# PCB_Telemetria_2020.net
KiCad netlist of a schematic drawn in EAGLE
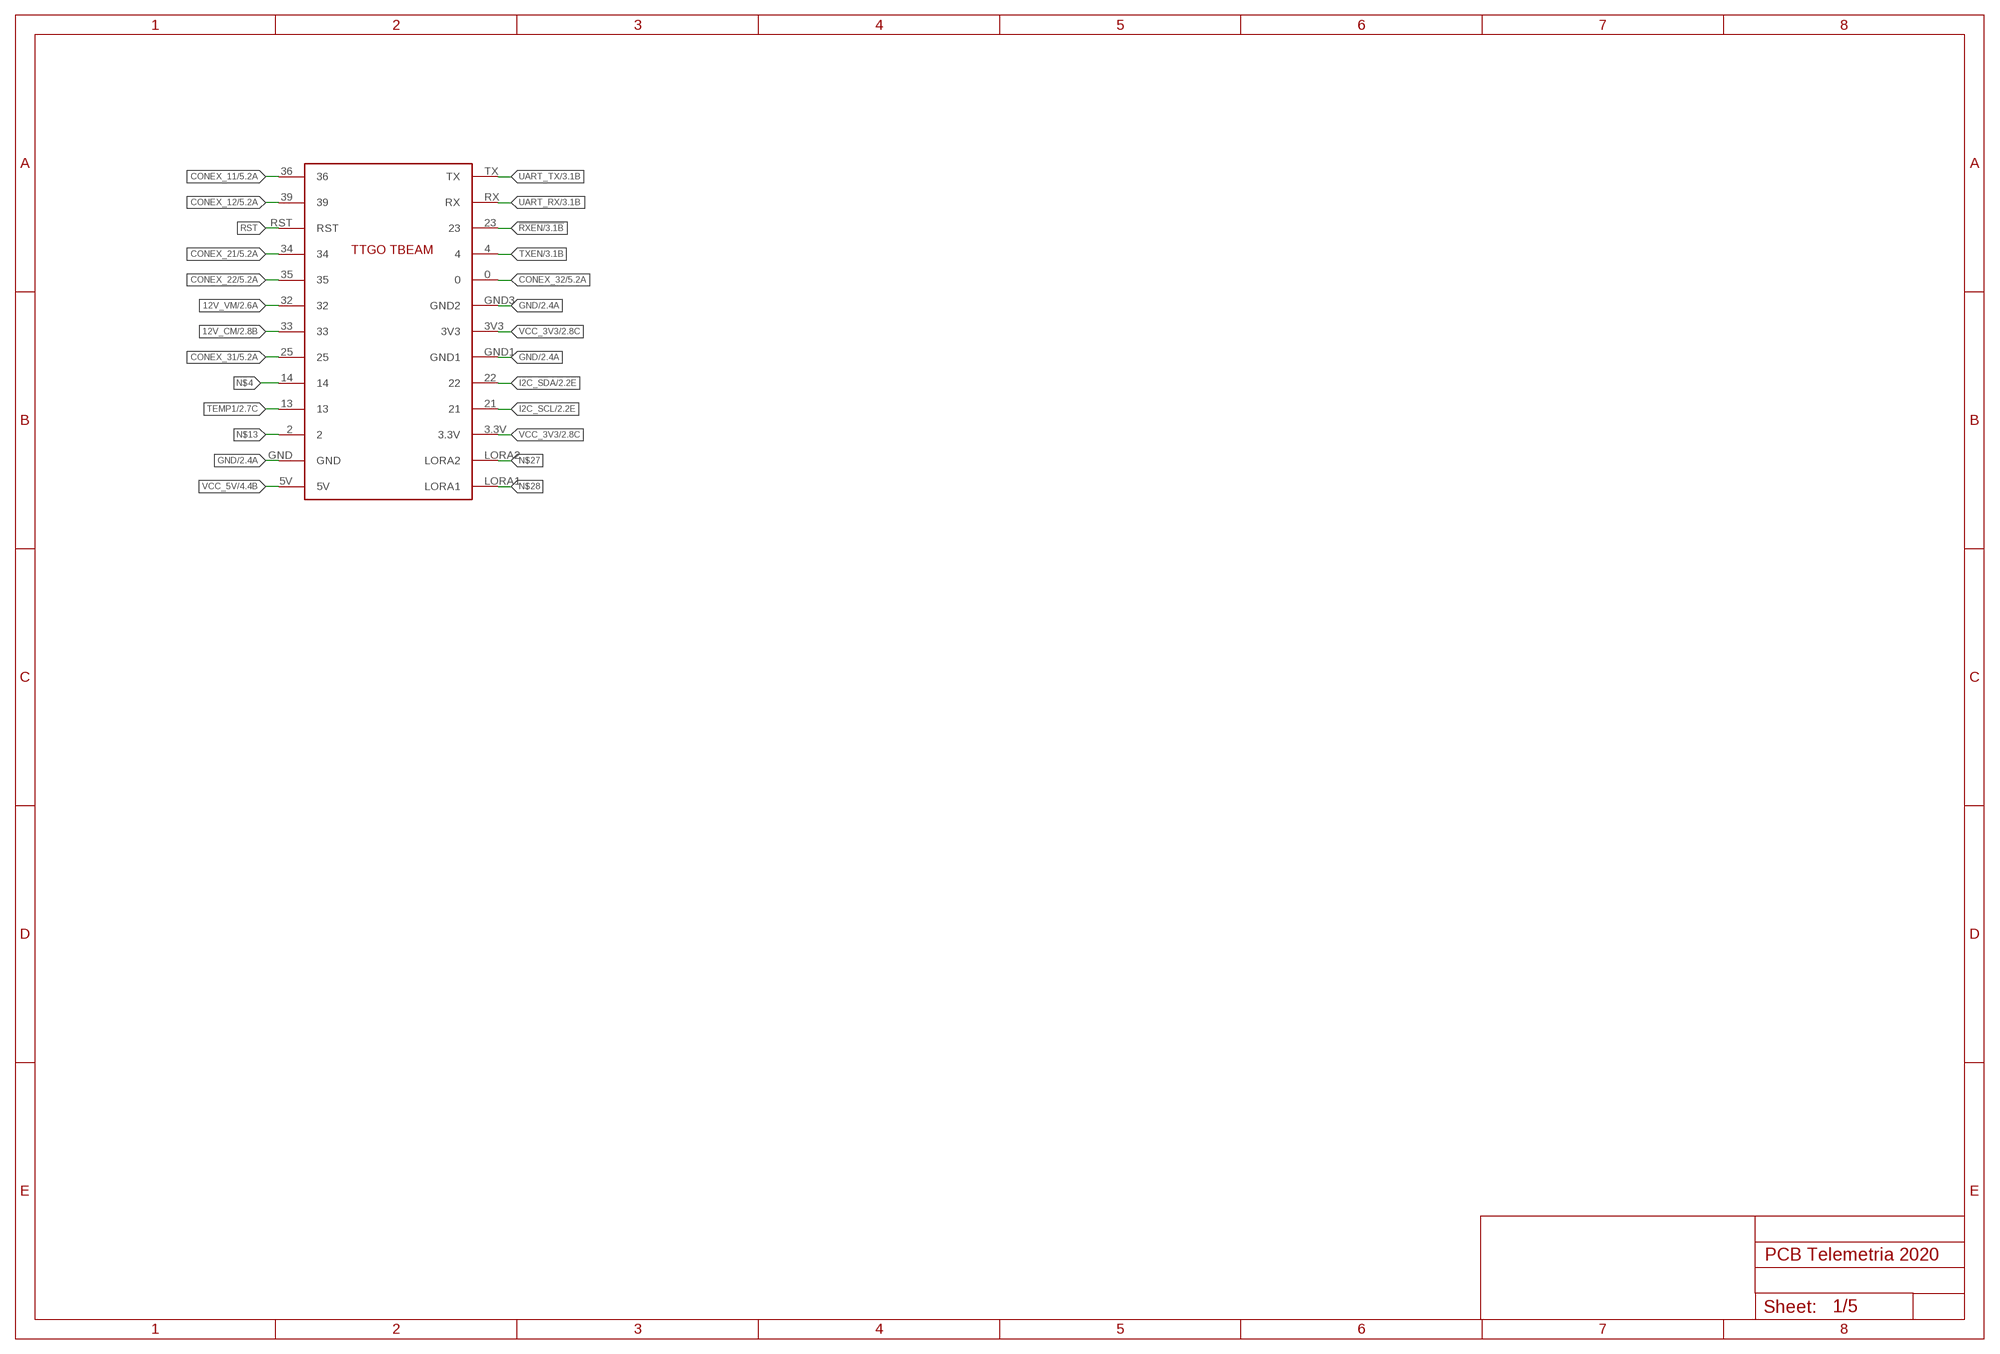
[diagram p0: schematic, sheet 1]
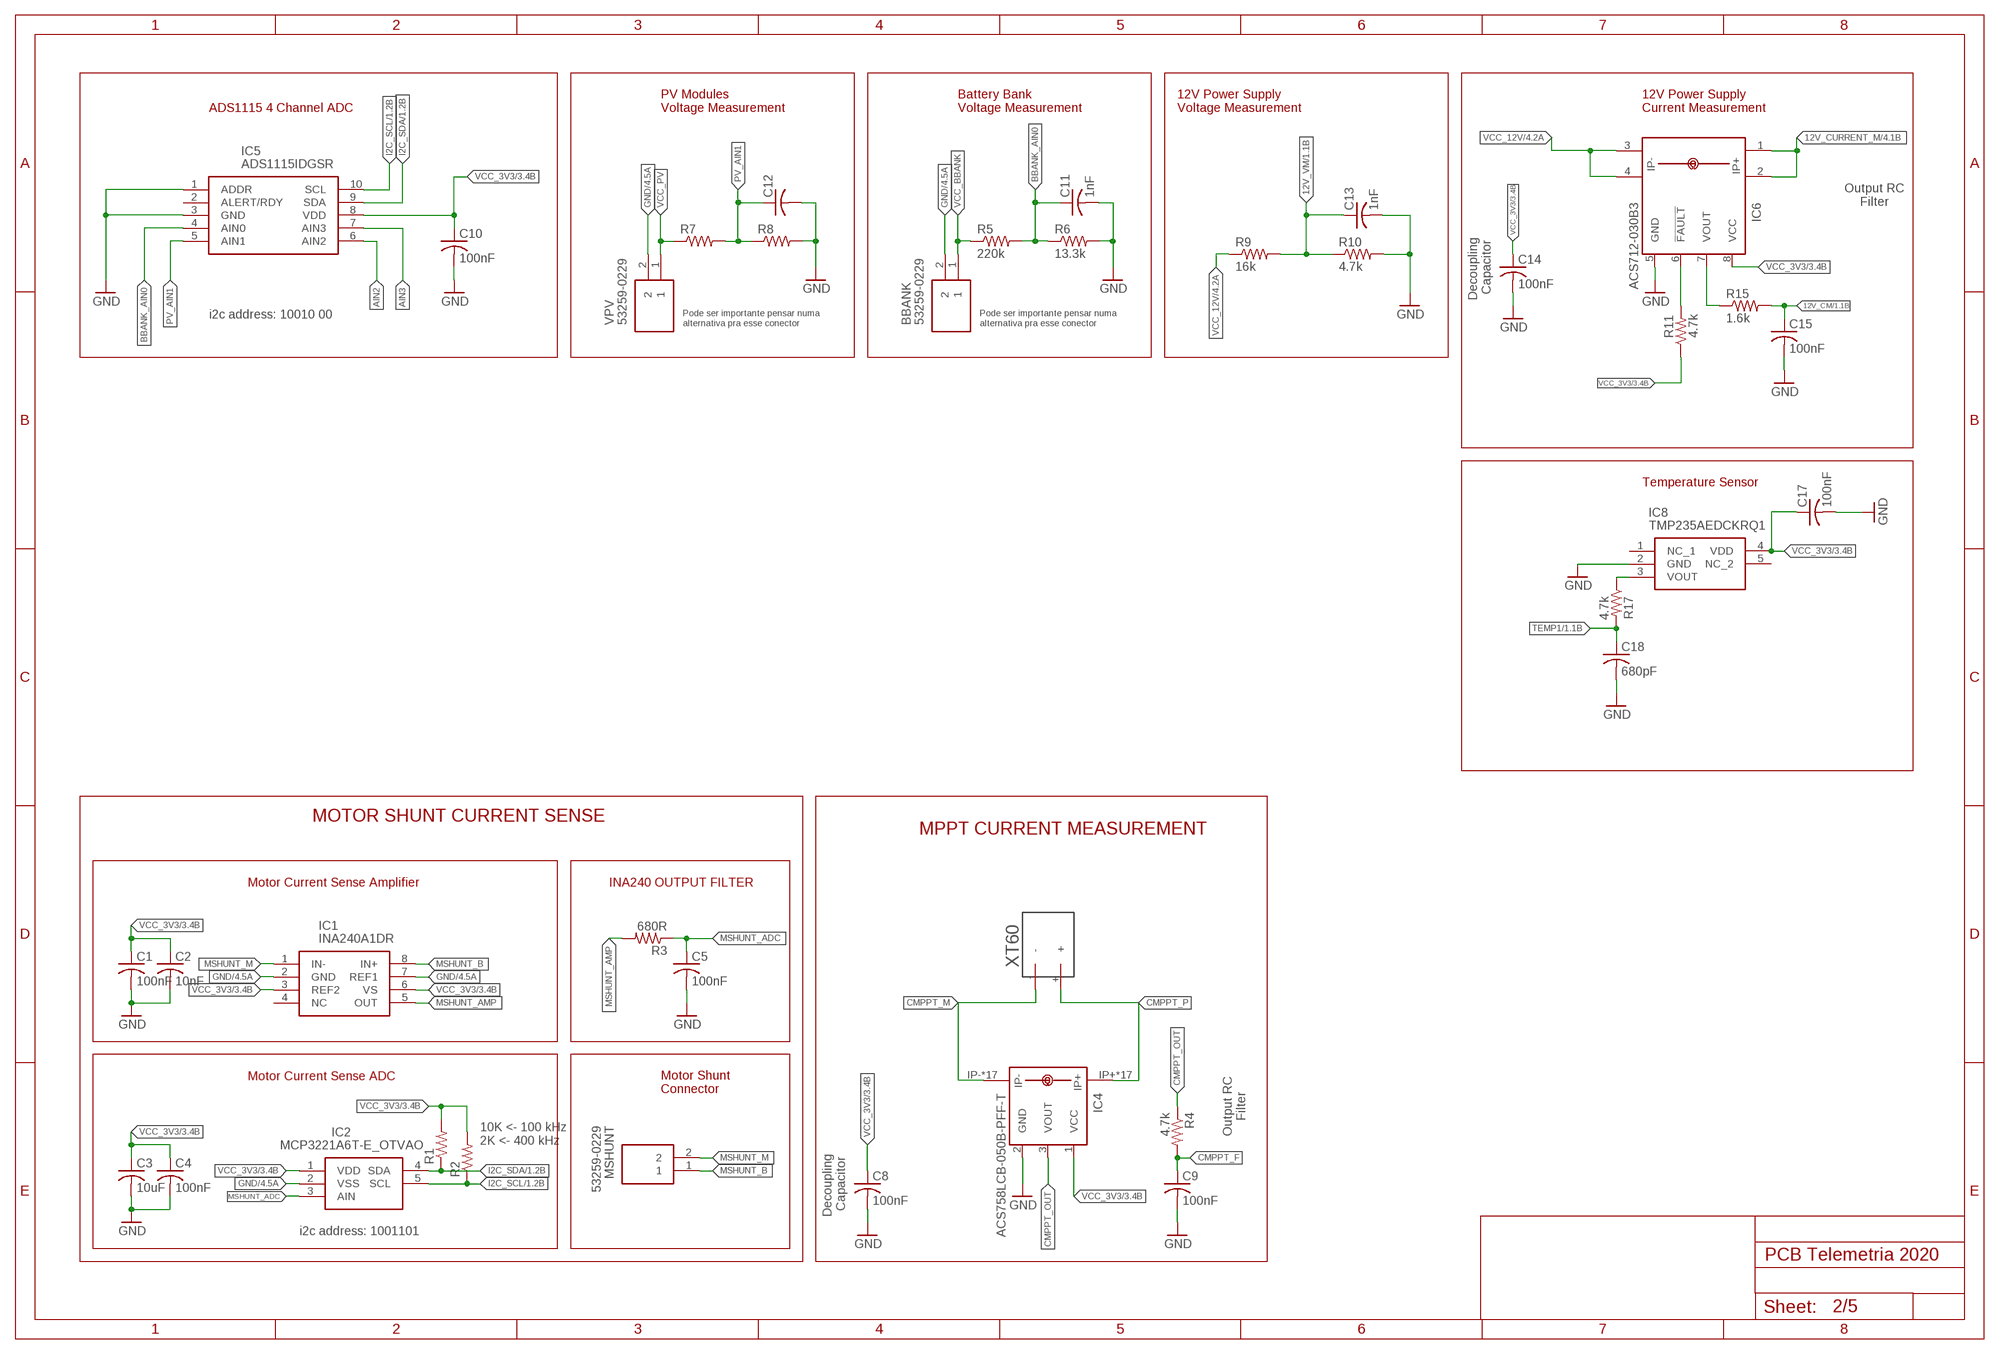
[diagram p1: schematic, sheet 2]
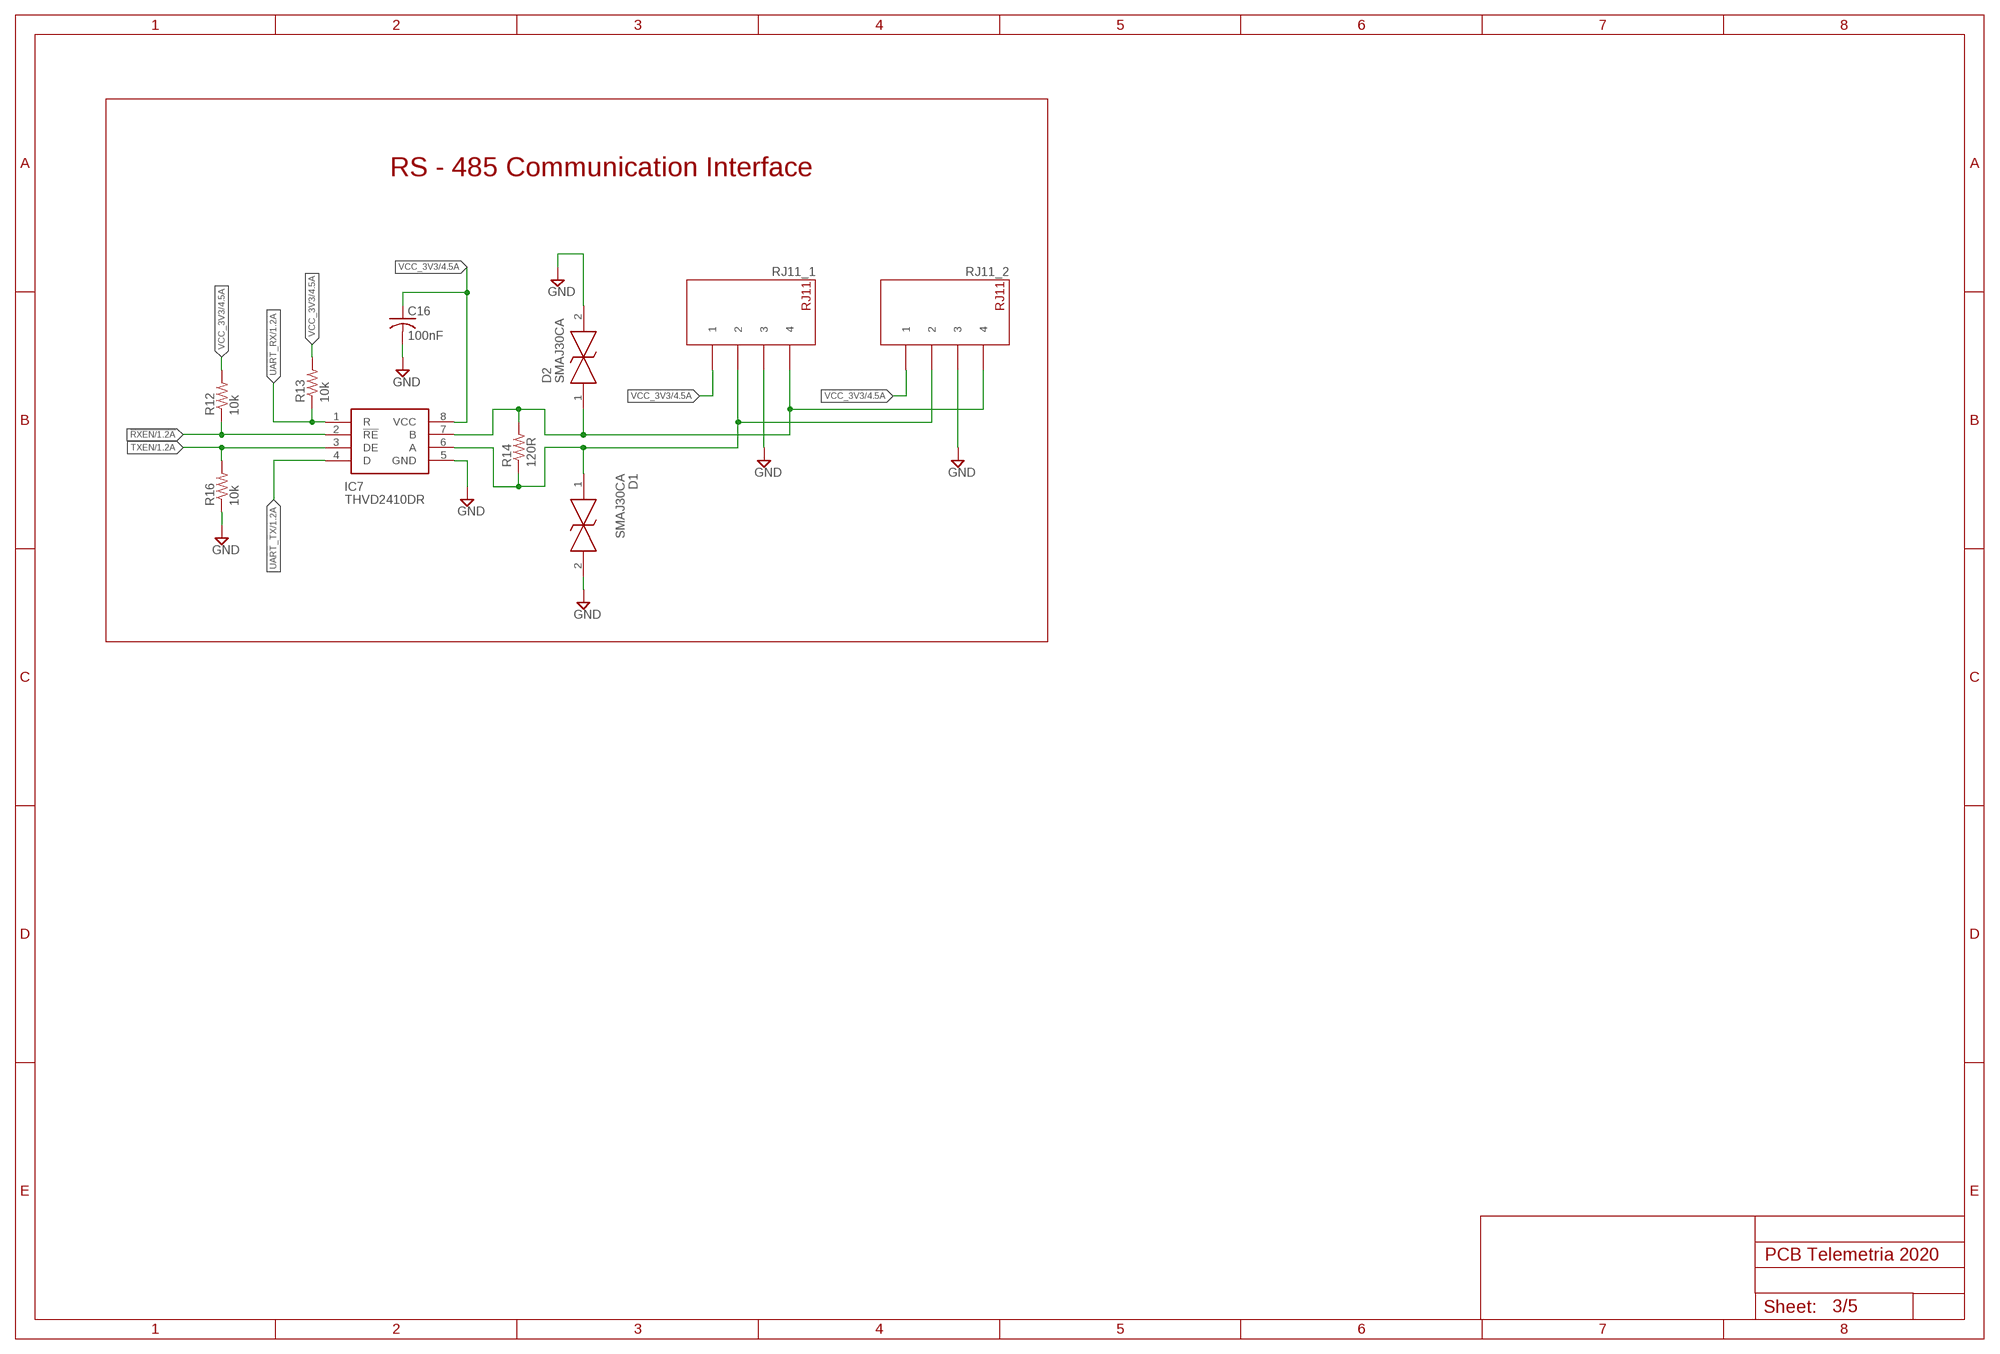
[diagram p2: schematic, sheet 3]
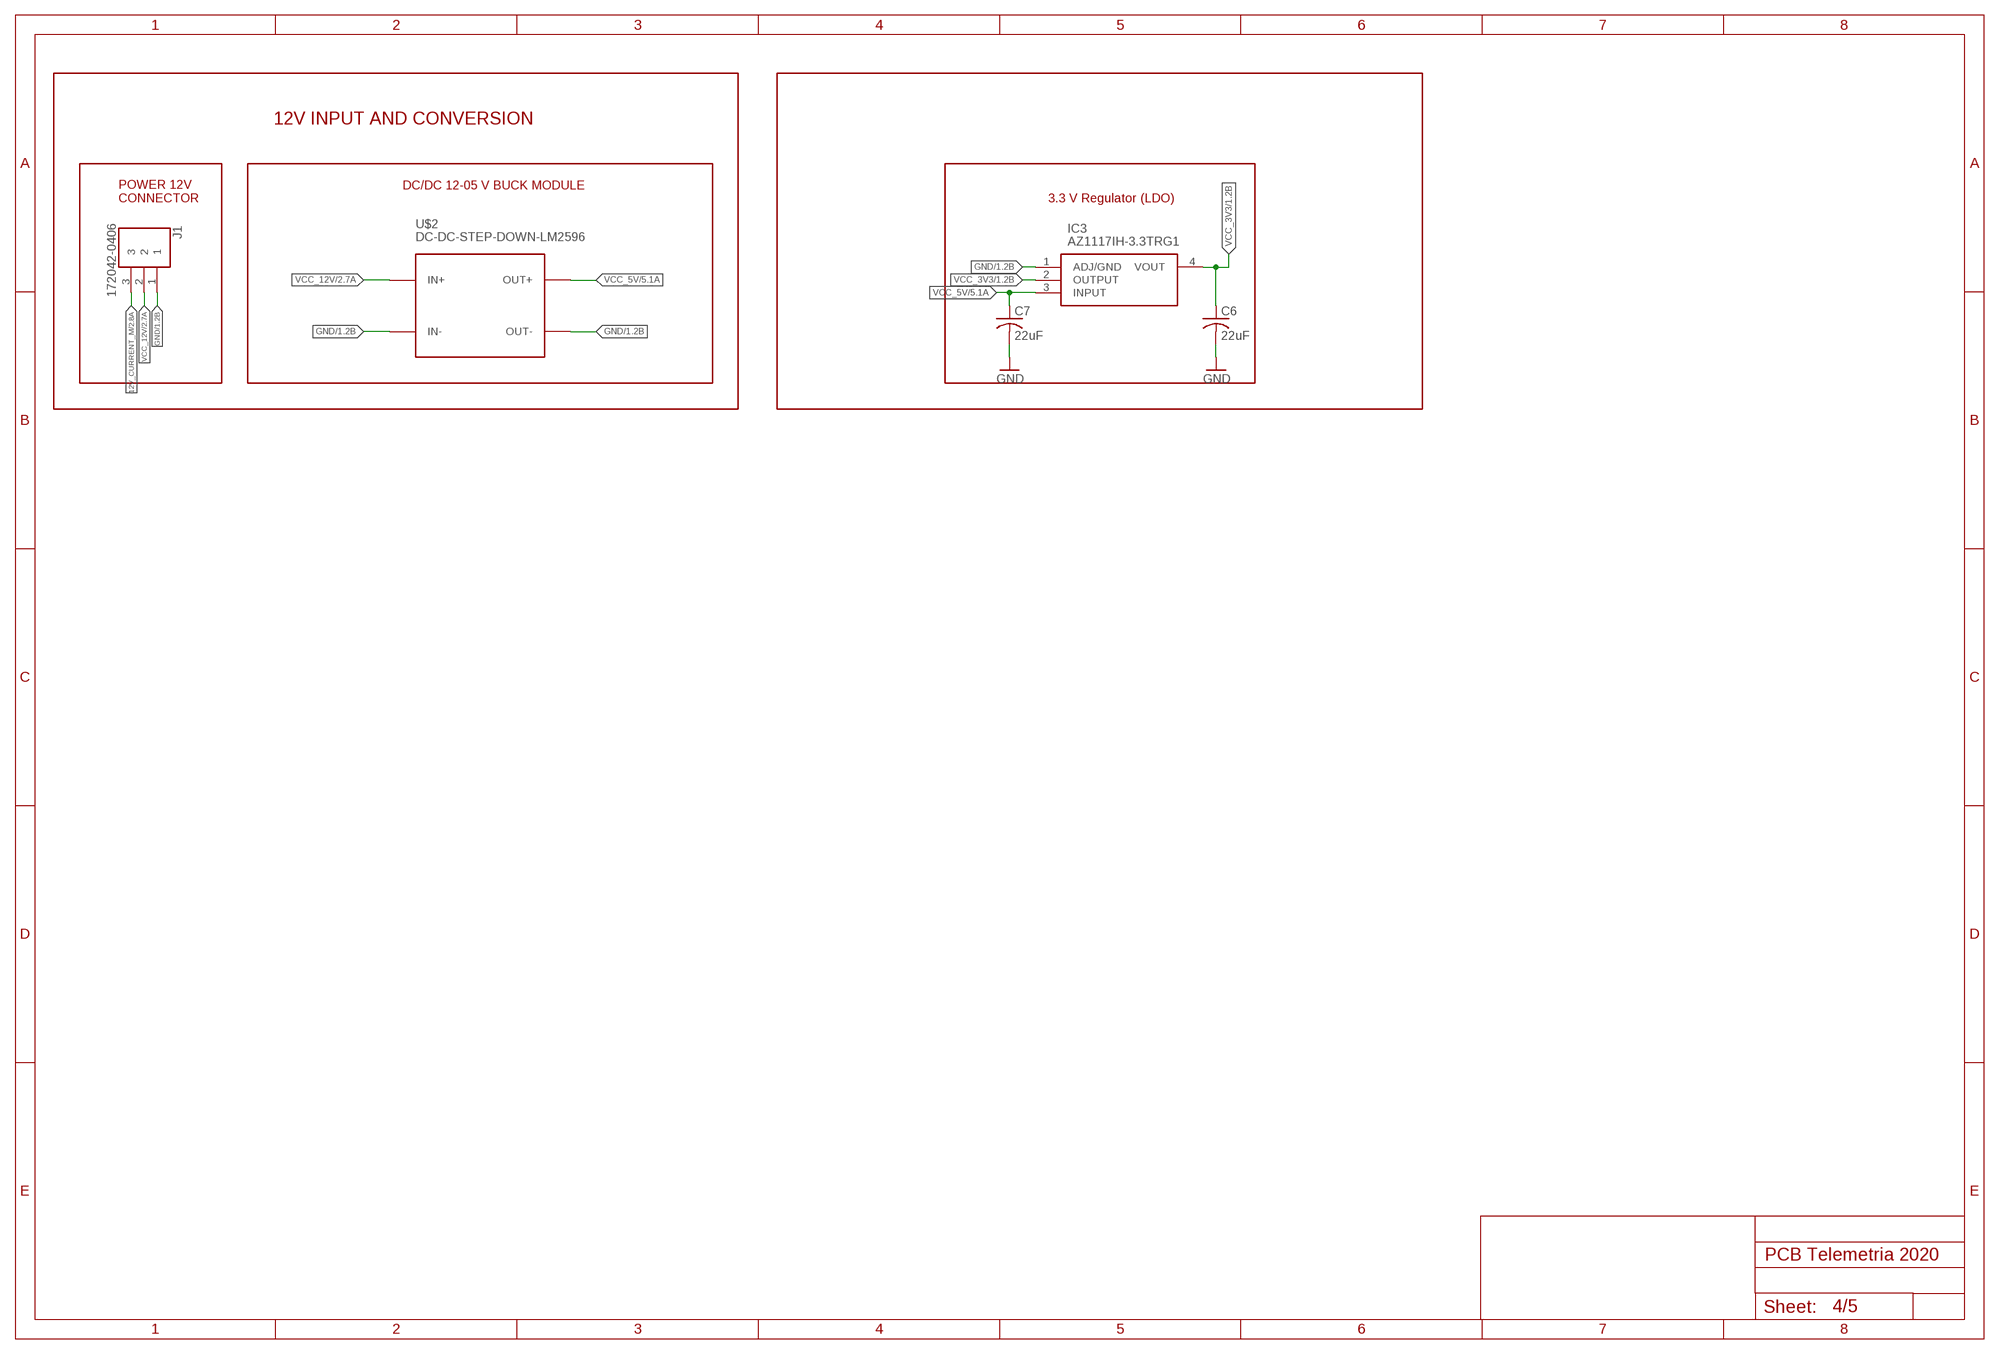
[diagram p3: schematic, sheet 4]
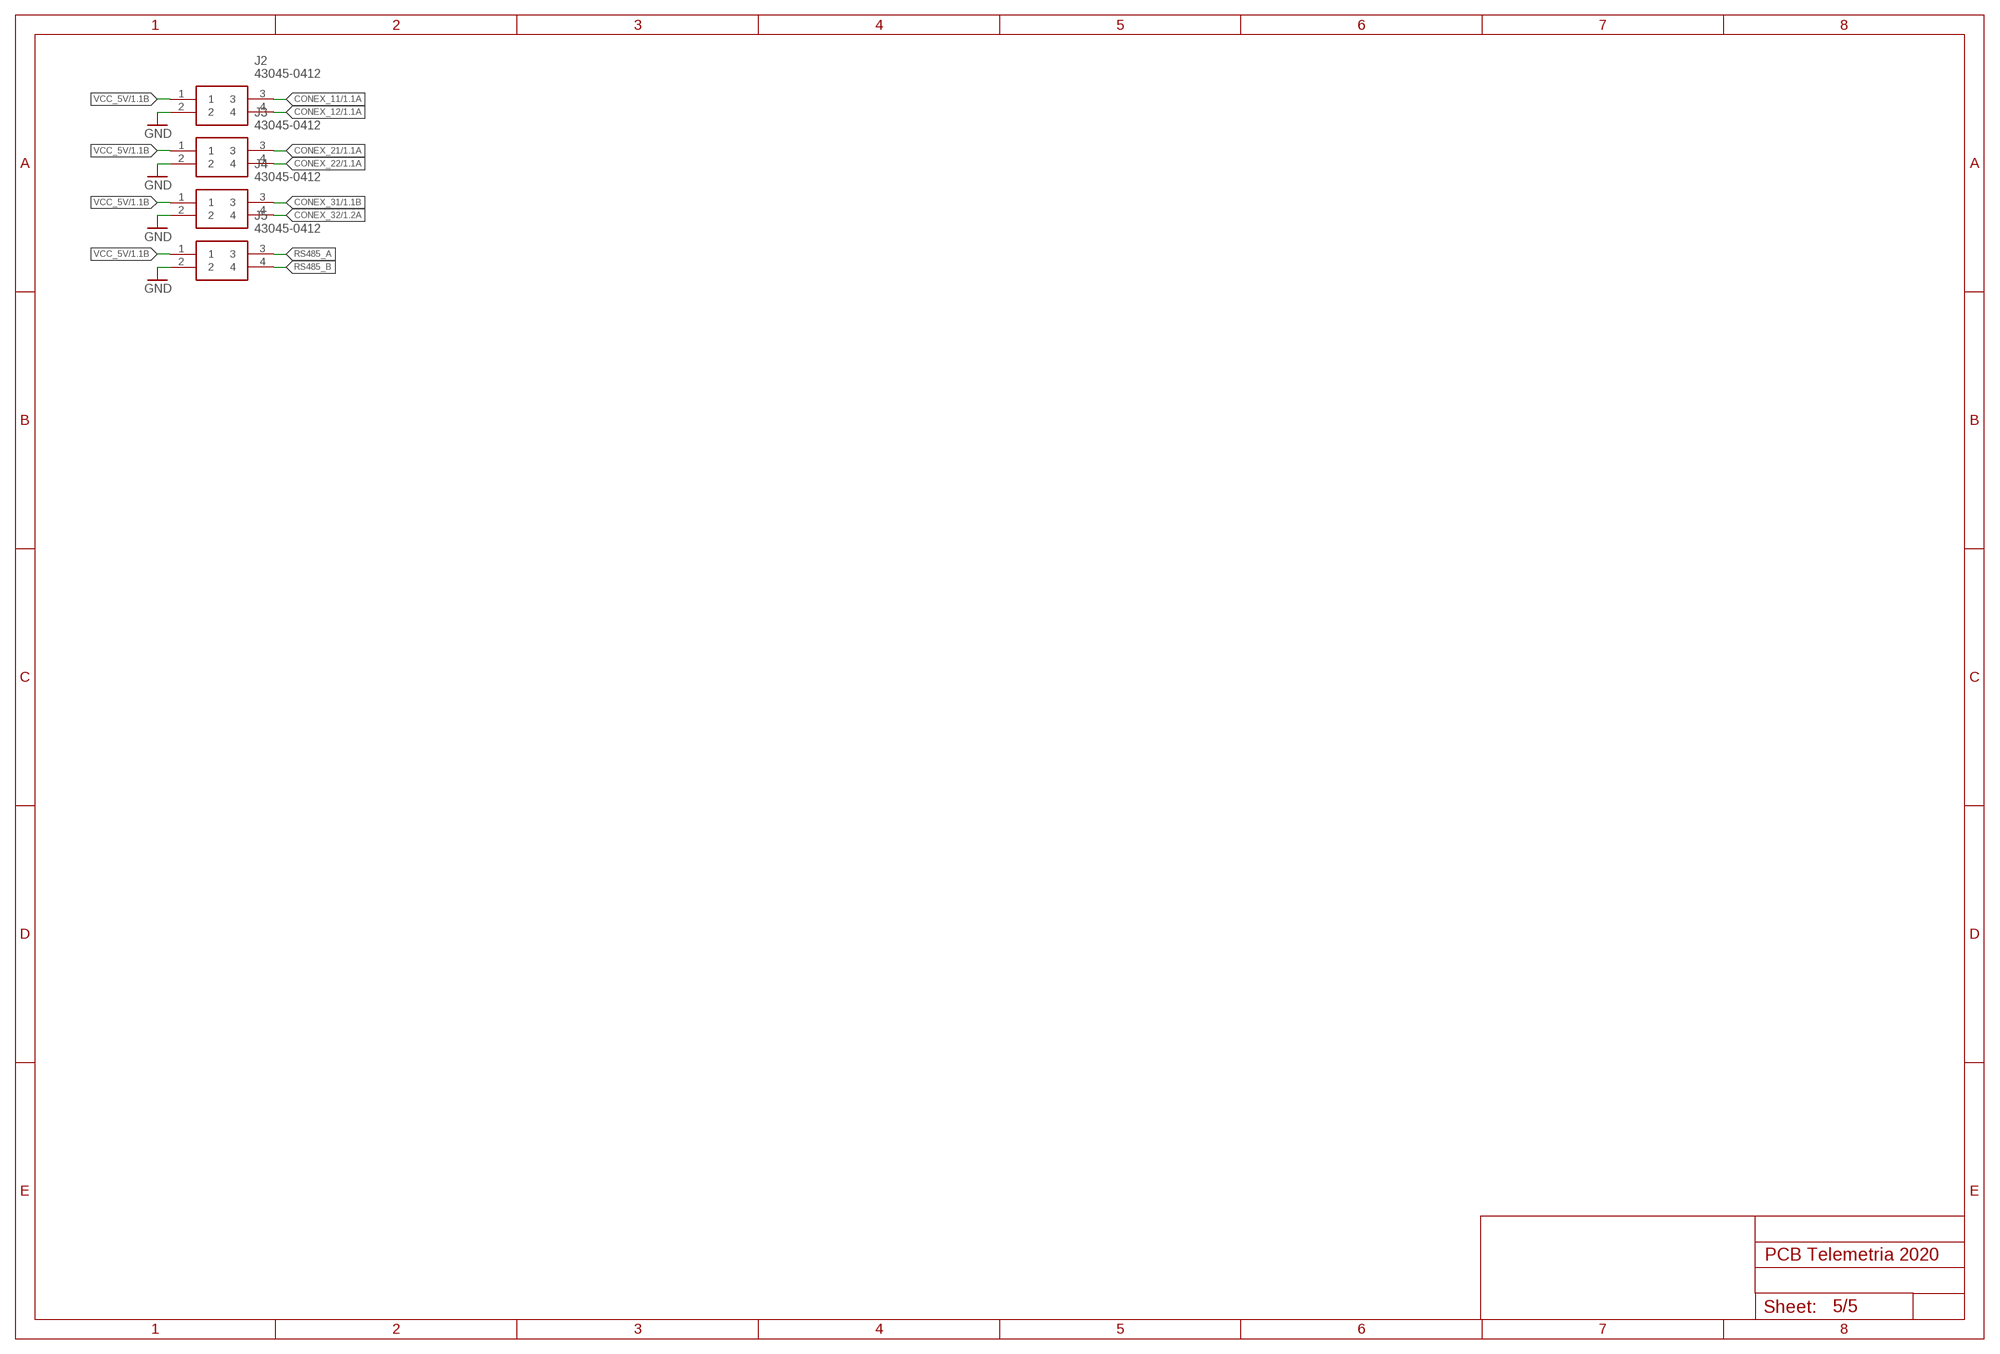
[diagram p4: schematic, sheet 5]

(export (version "E")
  (design (tool "Eeschema 10.0.6"))
  (components
    (comp (ref "U$1")
      (value "TTGOBEAM")
      (footprint "eagle-import:TTGOBEAM")
      (libsource (lib "eagle-import") (part "TTGOBEAM"))
    )
    (comp (ref "J2")
      (value "43045-0412")
      (footprint "eagle-import:43045-0412")
      (fields (field (name "MOUSER_PART_NUMBER") "538-43045-0412"))
      (libsource (lib "eagle-import") (part "43045-0412"))
    )
    (comp (ref "J3")
      (value "43045-0412")
      (footprint "eagle-import:43045-0412")
      (fields (field (name "MOUSER_PART_NUMBER") "538-43045-0412"))
      (libsource (lib "eagle-import") (part "43045-0412"))
    )
    (comp (ref "J4")
      (value "43045-0412")
      (footprint "eagle-import:43045-0412")
      (fields (field (name "MOUSER_PART_NUMBER") "538-43045-0412"))
      (libsource (lib "eagle-import") (part "43045-0412"))
    )
    (comp (ref "J5")
      (value "43045-0412")
      (footprint "eagle-import:43045-0412")
      (fields (field (name "MOUSER_PART_NUMBER") "538-43045-0412"))
      (libsource (lib "eagle-import") (part "43045-0412"))
    )
    (comp (ref "BBANK")
      (value "53259-0229")
      (footprint "eagle-import:0532590229")
      (fields (field (name "MOUSER_PART_NUMBER") "538-53259-0229"))
      (libsource (lib "eagle-import") (part "53259-0229"))
    )
    (comp (ref "C1")
      (value "100nF")
      (footprint "eagle-import:C0805")
      (libsource (lib "eagle-import") (part "C-USC0805"))
    )
    (comp (ref "C2")
      (value "10nF")
      (footprint "eagle-import:C0805")
      (libsource (lib "eagle-import") (part "C-USC0805"))
    )
    (comp (ref "C3")
      (value "10uF")
      (footprint "eagle-import:C0805")
      (libsource (lib "eagle-import") (part "C-USC0805"))
    )
    (comp (ref "C4")
      (value "100nF")
      (footprint "eagle-import:C0805")
      (libsource (lib "eagle-import") (part "C-USC0805"))
    )
    (comp (ref "C5")
      (value "100nF")
      (footprint "eagle-import:C0805")
      (libsource (lib "eagle-import") (part "C-USC0805"))
    )
    (comp (ref "C8")
      (value "100nF")
      (footprint "eagle-import:C0805")
      (libsource (lib "eagle-import") (part "C-USC0805"))
    )
    (comp (ref "C9")
      (value "100nF")
      (footprint "eagle-import:C0805")
      (libsource (lib "eagle-import") (part "C-USC0805"))
    )
    (comp (ref "C10")
      (value "100nF")
      (footprint "eagle-import:C0805")
      (libsource (lib "eagle-import") (part "C-USC0805"))
    )
    (comp (ref "C11")
      (value "1nF")
      (footprint "eagle-import:C0805")
      (libsource (lib "eagle-import") (part "C-USC0805"))
    )
    (comp (ref "C12")
      (value "C-USC0805")
      (footprint "eagle-import:C0805")
      (libsource (lib "eagle-import") (part "C-USC0805"))
    )
    (comp (ref "C13")
      (value "1nF")
      (footprint "eagle-import:C0805")
      (libsource (lib "eagle-import") (part "C-USC0805"))
    )
    (comp (ref "C14")
      (value "100nF")
      (footprint "eagle-import:C0805")
      (libsource (lib "eagle-import") (part "C-USC0805"))
    )
    (comp (ref "C15")
      (value "100nF")
      (footprint "eagle-import:C0805")
      (libsource (lib "eagle-import") (part "C-USC0805"))
    )
    (comp (ref "C17")
      (value "100nF")
      (footprint "eagle-import:C0805")
      (libsource (lib "eagle-import") (part "C-USC0805"))
    )
    (comp (ref "C18")
      (value "680pF")
      (footprint "eagle-import:C0805")
      (libsource (lib "eagle-import") (part "C-USC0805"))
    )
    (comp (ref "IC1")
      (value "INA240A1DR")
      (footprint "eagle-import:SOIC127P600X175-8N")
      (fields (field (name "MOUSER_PART_NUMBER") "595-INA240A1DR"))
      (libsource (lib "eagle-import") (part "INA240A1DR"))
    )
    (comp (ref "IC2")
      (value "MCP3221A6T-E_OTVAO")
      (footprint "eagle-import:SOT95P280X145-5N")
      (fields
        (field (name "MANUFACTURER_PART_NUMBER") "MCP3221A6T-E/OTVAO")
        (field (name "MOUSER_PART_NUMBER") "579-MCP3221A6TEOTVAO")
      )
      (libsource (lib "eagle-import") (part "MCP3221A6T-E_OTVAO"))
    )
    (comp (ref "IC4")
      (value "ACS758LCB-050B-PFF-T")
      (footprint "eagle-import:CB-PFF")
      (libsource (lib "eagle-import") (part "ACS758LCB-050B-PFF-T"))
    )
    (comp (ref "IC5")
      (value "ADS1115IDGSR")
      (footprint "eagle-import:SOP50P490X110-10N")
      (fields (field (name "MOUSER_PART_NUMBER") "595-ADS1115IDGSR"))
      (libsource (lib "eagle-import") (part "ADS1115IDGSR"))
    )
    (comp (ref "IC6")
      (value "ACS712-030B3")
      (footprint "eagle-import:SOIC8")
      (libsource (lib "eagle-import") (part "ACS712-LC"))
    )
    (comp (ref "IC8")
      (value "TMP235AEDCKRQ1")
      (footprint "eagle-import:SOT65P210X110-5N")
      (fields (field (name "MOUSER_PART_NUMBER") "595-TMP235AEDCKRQ1"))
      (libsource (lib "eagle-import") (part "TMP235AEDCKRQ1"))
    )
    (comp (ref "MSHUNT")
      (value "53259-0229")
      (footprint "eagle-import:0532590229")
      (fields (field (name "MOUSER_PART_NUMBER") "538-53259-0229"))
      (libsource (lib "eagle-import") (part "53259-0229"))
    )
    (comp (ref "R1")
      (value "R-US_R0805")
      (footprint "eagle-import:R0805")
      (libsource (lib "eagle-import") (part "R-US_R0805"))
    )
    (comp (ref "R2")
      (value "R-US_R0805")
      (footprint "eagle-import:R0805")
      (libsource (lib "eagle-import") (part "R-US_R0805"))
    )
    (comp (ref "R3")
      (value "680R")
      (footprint "eagle-import:R0805")
      (libsource (lib "eagle-import") (part "R-US_R0805"))
    )
    (comp (ref "R4")
      (value "4.7k")
      (footprint "eagle-import:R0805")
      (libsource (lib "eagle-import") (part "R-US_R0805"))
    )
    (comp (ref "R5")
      (value "220k")
      (footprint "eagle-import:R0805")
      (libsource (lib "eagle-import") (part "R-US_R0805"))
    )
    (comp (ref "R6")
      (value "13.3k")
      (footprint "eagle-import:R0805")
      (libsource (lib "eagle-import") (part "R-US_R0805"))
    )
    (comp (ref "R7")
      (value "R-US_R0805")
      (footprint "eagle-import:R0805")
      (libsource (lib "eagle-import") (part "R-US_R0805"))
    )
    (comp (ref "R8")
      (value "R-US_R0805")
      (footprint "eagle-import:R0805")
      (libsource (lib "eagle-import") (part "R-US_R0805"))
    )
    (comp (ref "R9")
      (value "16k")
      (footprint "eagle-import:R0805")
      (libsource (lib "eagle-import") (part "R-US_R0805"))
    )
    (comp (ref "R10")
      (value "4.7k")
      (footprint "eagle-import:R0805")
      (libsource (lib "eagle-import") (part "R-US_R0805"))
    )
    (comp (ref "R11")
      (value "4.7k")
      (footprint "eagle-import:R0805")
      (libsource (lib "eagle-import") (part "R-US_R0805"))
    )
    (comp (ref "R15")
      (value "1.6k")
      (footprint "eagle-import:R0805")
      (libsource (lib "eagle-import") (part "R-US_R0805"))
    )
    (comp (ref "R17")
      (value "4.7k")
      (footprint "eagle-import:R0805")
      (libsource (lib "eagle-import") (part "R-US_R0805"))
    )
    (comp (ref "U$3")
      (value "XT60")
      (footprint "eagle-import:XT60")
      (libsource (lib "eagle-import") (part "XT60"))
    )
    (comp (ref "VPV")
      (value "53259-0229")
      (footprint "eagle-import:0532590229")
      (fields (field (name "MOUSER_PART_NUMBER") "538-53259-0229"))
      (libsource (lib "eagle-import") (part "53259-0229"))
    )
    (comp (ref "C6")
      (value "22uF")
      (footprint "eagle-import:C0805")
      (libsource (lib "eagle-import") (part "C-USC0805"))
    )
    (comp (ref "C7")
      (value "22uF")
      (footprint "eagle-import:C0805")
      (libsource (lib "eagle-import") (part "C-USC0805"))
    )
    (comp (ref "IC3")
      (value "AZ1117IH-3.3TRG1")
      (footprint "eagle-import:SOT230P700X170-4N")
      (fields (field (name "MOUSER_PART_NUMBER") "621-AZ1117IH-3.3TRG1"))
      (libsource (lib "eagle-import") (part "AZ1117IH-3.3TRG1"))
    )
    (comp (ref "J1")
      (value "172042-0406")
      (footprint "eagle-import:MOLEX_172042-0406")
      (fields (field (name "MF") "Molex") (field (name "MP") "172042-0302"))
      (libsource (lib "eagle-import") (part "172042-0406"))
    )
    (comp (ref "U$2")
      (value "DC-DC-STEP-DOWN-LM2596")
      (footprint "eagle-import:DC-DC-STEP-DOWN-LM2596")
      (libsource (lib "eagle-import") (part "DC-DC-STEP-DOWN-LM2596"))
    )
    (comp (ref "C16")
      (value "100nF")
      (footprint "eagle-import:C0805")
      (libsource (lib "eagle-import") (part "C-USC0805"))
    )
    (comp (ref "D1")
      (value "SMAJ30CA")
      (footprint "eagle-import:DIONM5026X229N")
      (fields (field (name "MOUSER_PART_NUMBER") "576-SMAJ30CA"))
      (libsource (lib "eagle-import") (part "SMAJ30CA"))
    )
    (comp (ref "D2")
      (value "SMAJ30CA")
      (footprint "eagle-import:DIONM5026X229N")
      (fields (field (name "MOUSER_PART_NUMBER") "576-SMAJ30CA"))
      (libsource (lib "eagle-import") (part "SMAJ30CA"))
    )
    (comp (ref "IC7")
      (value "THVD2410DR")
      (footprint "eagle-import:SOIC127P600X175-8N")
      (fields (field (name "MOUSER_PART_NUMBER") "595-THVD2410DR"))
      (libsource (lib "eagle-import") (part "THVD2410DR"))
    )
    (comp (ref "R12")
      (value "10k")
      (footprint "eagle-import:M0805")
      (libsource (lib "eagle-import") (part "R-US_M0805"))
    )
    (comp (ref "R13")
      (value "10k")
      (footprint "eagle-import:M0805")
      (libsource (lib "eagle-import") (part "R-US_M0805"))
    )
    (comp (ref "R14")
      (value "120R")
      (footprint "eagle-import:M0805")
      (libsource (lib "eagle-import") (part "R-US_M0805"))
    )
    (comp (ref "R16")
      (value "10k")
      (footprint "eagle-import:M0805")
      (libsource (lib "eagle-import") (part "R-US_M0805"))
    )
    (comp (ref "RJ11_1")
      (value "TFC44")
      (footprint "eagle-import:TFC44")
      (libsource (lib "eagle-import") (part "TFC44"))
    )
    (comp (ref "RJ11_2")
      (value "TFC44")
      (footprint "eagle-import:TFC44")
      (libsource (lib "eagle-import") (part "TFC44"))
    )
  )
  (nets
    (net (code "1") (name "12V_CM") (class "Default")
      (node (ref "C15") (pin "1") (pinfunction "1_1") (pintype "passive"))
      (node (ref "R15") (pin "2") (pinfunction "2_2") (pintype "passive"))
      (node (ref "U$1") (pin "33") (pinfunction "33_33") (pintype "bidirectional"))
    )
    (net (code "2") (name "12V_CURRENT_M") (class "Default")
      (node (ref "IC6") (pin "1") (pinfunction "IP+_1") (pintype "passive"))
      (node (ref "IC6") (pin "2") (pinfunction "IP+1_2") (pintype "passive"))
      (node (ref "J1") (pin "3") (pinfunction "3_3") (pintype "passive"))
    )
    (net (code "3") (name "12V_VM") (class "Default")
      (node (ref "C13") (pin "1") (pinfunction "1_1") (pintype "passive"))
      (node (ref "R10") (pin "1") (pinfunction "1_1") (pintype "passive"))
      (node (ref "R9") (pin "2") (pinfunction "2_2") (pintype "passive"))
      (node (ref "U$1") (pin "32") (pinfunction "32_32") (pintype "bidirectional"))
    )
    (net (code "4") (name "AIN2") (class "Default")
      (node (ref "IC5") (pin "6") (pinfunction "AIN2_6") (pintype "bidirectional"))
    )
    (net (code "5") (name "AIN3") (class "Default")
      (node (ref "IC5") (pin "7") (pinfunction "AIN3_7") (pintype "bidirectional"))
    )
    (net (code "6") (name "BBANK_AIN0") (class "Default")
      (node (ref "C11") (pin "1") (pinfunction "1_1") (pintype "passive"))
      (node (ref "IC5") (pin "4") (pinfunction "AIN0_4") (pintype "bidirectional"))
      (node (ref "R5") (pin "2") (pinfunction "2_2") (pintype "passive"))
      (node (ref "R6") (pin "1") (pinfunction "1_1") (pintype "passive"))
    )
    (net (code "7") (name "CMPPT_F") (class "Default")
      (node (ref "C9") (pin "1") (pinfunction "1_1") (pintype "passive"))
      (node (ref "R4") (pin "2") (pinfunction "2_2") (pintype "passive"))
    )
    (net (code "8") (name "CMPPT_M") (class "Default")
      (node (ref "IC4") (pin "IP-") (pinfunction "IP-_IP-") (pintype "passive"))
      (node (ref "IC4") (pin "IP-@10") (pinfunction "IP-_IP-@10") (pintype "passive"))
      (node (ref "IC4") (pin "IP-@11") (pinfunction "IP-_IP-@11") (pintype "passive"))
      (node (ref "IC4") (pin "IP-@12") (pinfunction "IP-_IP-@12") (pintype "passive"))
      (node (ref "IC4") (pin "IP-@13") (pinfunction "IP-_IP-@13") (pintype "passive"))
      (node (ref "IC4") (pin "IP-@14") (pinfunction "IP-_IP-@14") (pintype "passive"))
      (node (ref "IC4") (pin "IP-@15") (pinfunction "IP-_IP-@15") (pintype "passive"))
      (node (ref "IC4") (pin "IP-@16") (pinfunction "IP-_IP-@16") (pintype "passive"))
      (node (ref "IC4") (pin "IP-@17") (pinfunction "IP-_IP-@17") (pintype "passive"))
      (node (ref "IC4") (pin "IP-@2") (pinfunction "IP-_IP-@2") (pintype "passive"))
      (node (ref "IC4") (pin "IP-@3") (pinfunction "IP-_IP-@3") (pintype "passive"))
      (node (ref "IC4") (pin "IP-@4") (pinfunction "IP-_IP-@4") (pintype "passive"))
      (node (ref "IC4") (pin "IP-@5") (pinfunction "IP-_IP-@5") (pintype "passive"))
      (node (ref "IC4") (pin "IP-@6") (pinfunction "IP-_IP-@6") (pintype "passive"))
      (node (ref "IC4") (pin "IP-@7") (pinfunction "IP-_IP-@7") (pintype "passive"))
      (node (ref "IC4") (pin "IP-@8") (pinfunction "IP-_IP-@8") (pintype "passive"))
      (node (ref "IC4") (pin "IP-@9") (pinfunction "IP-_IP-@9") (pintype "passive"))
      (node (ref "U$3") (pin "-") (pinfunction "-_-") (pintype "bidirectional"))
    )
    (net (code "9") (name "CMPPT_OUT") (class "Default")
      (node (ref "IC4") (pin "3") (pinfunction "VOUT_3") (pintype "output"))
      (node (ref "R4") (pin "1") (pinfunction "1_1") (pintype "passive"))
    )
    (net (code "10") (name "CMPPT_P") (class "Default")
      (node (ref "IC4") (pin "IP+") (pinfunction "IP+_IP+") (pintype "passive"))
      (node (ref "IC4") (pin "IP+@10") (pinfunction "IP+_IP+@10") (pintype "passive"))
      (node (ref "IC4") (pin "IP+@11") (pinfunction "IP+_IP+@11") (pintype "passive"))
      (node (ref "IC4") (pin "IP+@12") (pinfunction "IP+_IP+@12") (pintype "passive"))
      (node (ref "IC4") (pin "IP+@13") (pinfunction "IP+_IP+@13") (pintype "passive"))
      (node (ref "IC4") (pin "IP+@14") (pinfunction "IP+_IP+@14") (pintype "passive"))
      (node (ref "IC4") (pin "IP+@15") (pinfunction "IP+_IP+@15") (pintype "passive"))
      (node (ref "IC4") (pin "IP+@16") (pinfunction "IP+_IP+@16") (pintype "passive"))
      (node (ref "IC4") (pin "IP+@17") (pinfunction "IP+_IP+@17") (pintype "passive"))
      (node (ref "IC4") (pin "IP+@2") (pinfunction "IP+_IP+@2") (pintype "passive"))
      (node (ref "IC4") (pin "IP+@3") (pinfunction "IP+_IP+@3") (pintype "passive"))
      (node (ref "IC4") (pin "IP+@4") (pinfunction "IP+_IP+@4") (pintype "passive"))
      (node (ref "IC4") (pin "IP+@5") (pinfunction "IP+_IP+@5") (pintype "passive"))
      (node (ref "IC4") (pin "IP+@6") (pinfunction "IP+_IP+@6") (pintype "passive"))
      (node (ref "IC4") (pin "IP+@7") (pinfunction "IP+_IP+@7") (pintype "passive"))
      (node (ref "IC4") (pin "IP+@8") (pinfunction "IP+_IP+@8") (pintype "passive"))
      (node (ref "IC4") (pin "IP+@9") (pinfunction "IP+_IP+@9") (pintype "passive"))
      (node (ref "U$3") (pin "+") (pinfunction "+_+") (pintype "bidirectional"))
    )
    (net (code "11") (name "CONEX_11") (class "Default")
      (node (ref "J2") (pin "3") (pinfunction "3_3") (pintype "bidirectional"))
      (node (ref "U$1") (pin "36") (pinfunction "36_36") (pintype "bidirectional"))
    )
    (net (code "12") (name "CONEX_12") (class "Default")
      (node (ref "J2") (pin "4") (pinfunction "4_4") (pintype "bidirectional"))
      (node (ref "U$1") (pin "39") (pinfunction "39_39") (pintype "bidirectional"))
    )
    (net (code "13") (name "CONEX_21") (class "Default")
      (node (ref "J3") (pin "3") (pinfunction "3_3") (pintype "bidirectional"))
      (node (ref "U$1") (pin "34") (pinfunction "34_34") (pintype "bidirectional"))
    )
    (net (code "14") (name "CONEX_22") (class "Default")
      (node (ref "J3") (pin "4") (pinfunction "4_4") (pintype "bidirectional"))
      (node (ref "U$1") (pin "35") (pinfunction "35_35") (pintype "bidirectional"))
    )
    (net (code "15") (name "CONEX_31") (class "Default")
      (node (ref "J4") (pin "3") (pinfunction "3_3") (pintype "bidirectional"))
      (node (ref "U$1") (pin "25") (pinfunction "25_25") (pintype "bidirectional"))
    )
    (net (code "16") (name "CONEX_32") (class "Default")
      (node (ref "J4") (pin "4") (pinfunction "4_4") (pintype "bidirectional"))
      (node (ref "U$1") (pin "0") (pinfunction "0_0") (pintype "bidirectional"))
    )
    (net (code "17") (name "GND") (class "Default")
      (node (ref "BBANK") (pin "2") (pinfunction "2_2") (pintype "bidirectional"))
      (node (ref "C1") (pin "2") (pinfunction "2_2") (pintype "passive"))
      (node (ref "C10") (pin "2") (pinfunction "2_2") (pintype "passive"))
      (node (ref "C11") (pin "2") (pinfunction "2_2") (pintype "passive"))
      (node (ref "C12") (pin "2") (pinfunction "2_2") (pintype "passive"))
      (node (ref "C13") (pin "2") (pinfunction "2_2") (pintype "passive"))
      (node (ref "C14") (pin "2") (pinfunction "2_2") (pintype "passive"))
      (node (ref "C15") (pin "2") (pinfunction "2_2") (pintype "passive"))
      (node (ref "C16") (pin "2") (pinfunction "2_2") (pintype "passive"))
      (node (ref "C17") (pin "2") (pinfunction "2_2") (pintype "passive"))
      (node (ref "C18") (pin "2") (pinfunction "2_2") (pintype "passive"))
      (node (ref "C2") (pin "2") (pinfunction "2_2") (pintype "passive"))
      (node (ref "C3") (pin "2") (pinfunction "2_2") (pintype "passive"))
      (node (ref "C4") (pin "2") (pinfunction "2_2") (pintype "passive"))
      (node (ref "C5") (pin "2") (pinfunction "2_2") (pintype "passive"))
      (node (ref "C6") (pin "2") (pinfunction "2_2") (pintype "passive"))
      (node (ref "C7") (pin "2") (pinfunction "2_2") (pintype "passive"))
      (node (ref "C8") (pin "2") (pinfunction "2_2") (pintype "passive"))
      (node (ref "C9") (pin "2") (pinfunction "2_2") (pintype "passive"))
      (node (ref "D1") (pin "2") (pinfunction "2_2") (pintype "bidirectional"))
      (node (ref "D2") (pin "2") (pinfunction "2_2") (pintype "bidirectional"))
      (node (ref "IC1") (pin "2") (pinfunction "GND_2") (pintype "bidirectional"))
      (node (ref "IC1") (pin "7") (pinfunction "REF1_7") (pintype "bidirectional"))
      (node (ref "IC2") (pin "2") (pinfunction "VSS_2") (pintype "bidirectional"))
      (node (ref "IC3") (pin "1") (pinfunction "ADJ/GND_1") (pintype "bidirectional"))
      (node (ref "IC4") (pin "2") (pinfunction "GND_2") (pintype "power_in"))
      (node (ref "IC5") (pin "1") (pinfunction "ADDR_1") (pintype "bidirectional"))
      (node (ref "IC5") (pin "3") (pinfunction "GND_3") (pintype "bidirectional"))
      (node (ref "IC6") (pin "5") (pinfunction "GND_5") (pintype "power_in"))
      (node (ref "IC7") (pin "5") (pinfunction "GND_5") (pintype "bidirectional"))
      (node (ref "IC8") (pin "2") (pinfunction "GND_2") (pintype "bidirectional"))
      (node (ref "J1") (pin "1") (pinfunction "1_1") (pintype "passive"))
      (node (ref "J2") (pin "2") (pinfunction "2_2") (pintype "bidirectional"))
      (node (ref "J3") (pin "2") (pinfunction "2_2") (pintype "bidirectional"))
      (node (ref "J4") (pin "2") (pinfunction "2_2") (pintype "bidirectional"))
      (node (ref "J5") (pin "2") (pinfunction "2_2") (pintype "bidirectional"))
      (node (ref "R10") (pin "2") (pinfunction "2_2") (pintype "passive"))
      (node (ref "R16") (pin "1") (pinfunction "1_1") (pintype "passive"))
      (node (ref "R6") (pin "2") (pinfunction "2_2") (pintype "passive"))
      (node (ref "R8") (pin "2") (pinfunction "2_2") (pintype "passive"))
      (node (ref "RJ11_1") (pin "P$3") (pinfunction "3_P$3") (pintype "bidirectional"))
      (node (ref "RJ11_2") (pin "P$3") (pinfunction "3_P$3") (pintype "bidirectional"))
      (node (ref "U$1") (pin "GND") (pinfunction "GND_GND") (pintype "bidirectional"))
      (node (ref "U$1") (pin "GND1") (pinfunction "GND1_GND1") (pintype "bidirectional"))
      (node (ref "U$1") (pin "GND3") (pinfunction "GND2_GND3") (pintype "bidirectional"))
      (node (ref "U$2") (pin "IN-") (pinfunction "IN-_IN-") (pintype "bidirectional"))
      (node (ref "U$2") (pin "OUT-") (pinfunction "OUT-_OUT-") (pintype "bidirectional"))
      (node (ref "VPV") (pin "2") (pinfunction "2_2") (pintype "bidirectional"))
    )
    (net (code "18") (name "I2C_SCL") (class "Default")
      (node (ref "IC2") (pin "5") (pinfunction "SCL_5") (pintype "bidirectional"))
      (node (ref "IC5") (pin "10") (pinfunction "SCL_10") (pintype "bidirectional"))
      (node (ref "R2") (pin "1") (pinfunction "1_1") (pintype "passive"))
      (node (ref "U$1") (pin "21") (pinfunction "21_21") (pintype "bidirectional"))
    )
    (net (code "19") (name "I2C_SDA") (class "Default")
      (node (ref "IC2") (pin "4") (pinfunction "SDA_4") (pintype "bidirectional"))
      (node (ref "IC5") (pin "9") (pinfunction "SDA_9") (pintype "bidirectional"))
      (node (ref "R1") (pin "1") (pinfunction "1_1") (pintype "passive"))
      (node (ref "U$1") (pin "22") (pinfunction "22_22") (pintype "bidirectional"))
    )
    (net (code "20") (name "MSHUNT_ADC") (class "Default")
      (node (ref "C5") (pin "1") (pinfunction "1_1") (pintype "passive"))
      (node (ref "IC2") (pin "3") (pinfunction "AIN_3") (pintype "bidirectional"))
      (node (ref "R3") (pin "1") (pinfunction "1_1") (pintype "passive"))
    )
    (net (code "21") (name "MSHUNT_AMP") (class "Default")
      (node (ref "IC1") (pin "5") (pinfunction "OUT_5") (pintype "bidirectional"))
      (node (ref "R3") (pin "2") (pinfunction "2_2") (pintype "passive"))
    )
    (net (code "22") (name "MSHUNT_B") (class "Default")
      (node (ref "IC1") (pin "8") (pinfunction "IN+_8") (pintype "bidirectional"))
      (node (ref "MSHUNT") (pin "1") (pinfunction "1_1") (pintype "bidirectional"))
    )
    (net (code "23") (name "MSHUNT_M") (class "Default")
      (node (ref "IC1") (pin "1") (pinfunction "IN-_1") (pintype "bidirectional"))
      (node (ref "MSHUNT") (pin "2") (pinfunction "2_2") (pintype "bidirectional"))
    )
    (net (code "24") (name "N$4") (class "Default")
      (node (ref "U$1") (pin "14") (pinfunction "14_14") (pintype "bidirectional"))
    )
    (net (code "25") (name "N$13") (class "Default")
      (node (ref "U$1") (pin "2") (pinfunction "2_2") (pintype "bidirectional"))
    )
    (net (code "26") (name "N$27") (class "Default")
      (node (ref "U$1") (pin "LORA2") (pinfunction "LORA2_LORA2") (pintype "bidirectional"))
    )
    (net (code "27") (name "N$28") (class "Default")
      (node (ref "U$1") (pin "LORA1") (pinfunction "LORA1_LORA1") (pintype "bidirectional"))
    )
    (net (code "28") (name "Net-(IC6-VOUT)") (class "Default")
      (node (ref "IC6") (pin "7") (pinfunction "VOUT_7") (pintype "output"))
      (node (ref "R15") (pin "1") (pinfunction "1_1") (pintype "passive"))
    )
    (net (code "29") (name "Net-(IC6-~{FAULT})") (class "Default")
      (node (ref "IC6") (pin "6") (pinfunction "~{FAULT}_6") (pintype "bidirectional"))
      (node (ref "R11") (pin "2") (pinfunction "2_2") (pintype "passive"))
    )
    (net (code "30") (name "Net-(IC8-VOUT)") (class "Default")
      (node (ref "IC8") (pin "3") (pinfunction "VOUT_3") (pintype "bidirectional"))
      (node (ref "R17") (pin "1") (pinfunction "1_1") (pintype "passive"))
    )
    (net (code "31") (name "PV_AIN1") (class "Default")
      (node (ref "C12") (pin "1") (pinfunction "1_1") (pintype "passive"))
      (node (ref "IC5") (pin "5") (pinfunction "AIN1_5") (pintype "bidirectional"))
      (node (ref "R7") (pin "2") (pinfunction "2_2") (pintype "passive"))
      (node (ref "R8") (pin "1") (pinfunction "1_1") (pintype "passive"))
    )
    (net (code "32") (name "RS485_A") (class "Default")
      (node (ref "D1") (pin "1") (pinfunction "1_1") (pintype "bidirectional"))
      (node (ref "IC7") (pin "6") (pinfunction "A_6") (pintype "bidirectional"))
      (node (ref "J5") (pin "3") (pinfunction "3_3") (pintype "bidirectional"))
      (node (ref "R14") (pin "1") (pinfunction "1_1") (pintype "passive"))
      (node (ref "RJ11_1") (pin "P$2") (pinfunction "2_P$2") (pintype "bidirectional"))
      (node (ref "RJ11_2") (pin "P$2") (pinfunction "2_P$2") (pintype "bidirectional"))
    )
    (net (code "33") (name "RS485_B") (class "Default")
      (node (ref "D2") (pin "1") (pinfunction "1_1") (pintype "bidirectional"))
      (node (ref "IC7") (pin "7") (pinfunction "B_7") (pintype "bidirectional"))
      (node (ref "J5") (pin "4") (pinfunction "4_4") (pintype "bidirectional"))
      (node (ref "R14") (pin "2") (pinfunction "2_2") (pintype "passive"))
      (node (ref "RJ11_1") (pin "P$4") (pinfunction "4_P$4") (pintype "bidirectional"))
      (node (ref "RJ11_2") (pin "P$4") (pinfunction "4_P$4") (pintype "bidirectional"))
    )
    (net (code "34") (name "RST") (class "Default")
      (node (ref "U$1") (pin "RST") (pinfunction "RST_RST") (pintype "bidirectional"))
    )
    (net (code "35") (name "TEMP1") (class "Default")
      (node (ref "C18") (pin "1") (pinfunction "1_1") (pintype "passive"))
      (node (ref "R17") (pin "2") (pinfunction "2_2") (pintype "passive"))
      (node (ref "U$1") (pin "13") (pinfunction "13_13") (pintype "bidirectional"))
    )
    (net (code "36") (name "TXEN") (class "Default")
      (node (ref "IC7") (pin "3") (pinfunction "DE_3") (pintype "bidirectional"))
      (node (ref "R16") (pin "2") (pinfunction "2_2") (pintype "passive"))
      (node (ref "U$1") (pin "4") (pinfunction "4_4") (pintype "bidirectional"))
    )
    (net (code "37") (name "UART_RX") (class "Default")
      (node (ref "IC7") (pin "1") (pinfunction "R_1") (pintype "bidirectional"))
      (node (ref "R13") (pin "1") (pinfunction "1_1") (pintype "passive"))
      (node (ref "U$1") (pin "RX") (pinfunction "RX_RX") (pintype "bidirectional"))
    )
    (net (code "38") (name "UART_TX") (class "Default")
      (node (ref "IC7") (pin "4") (pinfunction "D_4") (pintype "bidirectional"))
      (node (ref "U$1") (pin "TX") (pinfunction "TX_TX") (pintype "bidirectional"))
    )
    (net (code "39") (name "VCC_3V3") (class "Default")
      (node (ref "C1") (pin "1") (pinfunction "1_1") (pintype "passive"))
      (node (ref "C10") (pin "1") (pinfunction "1_1") (pintype "passive"))
      (node (ref "C14") (pin "1") (pinfunction "1_1") (pintype "passive"))
      (node (ref "C16") (pin "1") (pinfunction "1_1") (pintype "passive"))
      (node (ref "C17") (pin "1") (pinfunction "1_1") (pintype "passive"))
      (node (ref "C2") (pin "1") (pinfunction "1_1") (pintype "passive"))
      (node (ref "C3") (pin "1") (pinfunction "1_1") (pintype "passive"))
      (node (ref "C4") (pin "1") (pinfunction "1_1") (pintype "passive"))
      (node (ref "C6") (pin "1") (pinfunction "1_1") (pintype "passive"))
      (node (ref "C8") (pin "1") (pinfunction "1_1") (pintype "passive"))
      (node (ref "IC1") (pin "3") (pinfunction "REF2_3") (pintype "bidirectional"))
      (node (ref "IC1") (pin "6") (pinfunction "VS_6") (pintype "bidirectional"))
      (node (ref "IC2") (pin "1") (pinfunction "VDD_1") (pintype "bidirectional"))
      (node (ref "IC3") (pin "2") (pinfunction "OUTPUT_2") (pintype "bidirectional"))
      (node (ref "IC3") (pin "4") (pinfunction "VOUT_4") (pintype "bidirectional"))
      (node (ref "IC4") (pin "1") (pinfunction "VCC_1") (pintype "power_in"))
      (node (ref "IC5") (pin "8") (pinfunction "VDD_8") (pintype "bidirectional"))
      (node (ref "IC6") (pin "8") (pinfunction "VCC_8") (pintype "power_in"))
      (node (ref "IC7") (pin "8") (pinfunction "VCC_8") (pintype "bidirectional"))
      (node (ref "IC8") (pin "4") (pinfunction "VDD_4") (pintype "bidirectional"))
      (node (ref "R1") (pin "2") (pinfunction "2_2") (pintype "passive"))
      (node (ref "R11") (pin "1") (pinfunction "1_1") (pintype "passive"))
      (node (ref "R12") (pin "2") (pinfunction "2_2") (pintype "passive"))
      (node (ref "R13") (pin "2") (pinfunction "2_2") (pintype "passive"))
      (node (ref "R2") (pin "2") (pinfunction "2_2") (pintype "passive"))
      (node (ref "RJ11_1") (pin "P$1") (pinfunction "1_P$1") (pintype "bidirectional"))
      (node (ref "RJ11_2") (pin "P$1") (pinfunction "1_P$1") (pintype "bidirectional"))
      (node (ref "U$1") (pin "3.3V") (pinfunction "3.3V_3.3V") (pintype "bidirectional"))
      (node (ref "U$1") (pin "3V3") (pinfunction "3V3_3V3") (pintype "bidirectional"))
    )
    (net (code "40") (name "VCC_5V") (class "Default")
      (node (ref "C7") (pin "1") (pinfunction "1_1") (pintype "passive"))
      (node (ref "IC3") (pin "3") (pinfunction "INPUT_3") (pintype "bidirectional"))
      (node (ref "J2") (pin "1") (pinfunction "1_1") (pintype "bidirectional"))
      (node (ref "J3") (pin "1") (pinfunction "1_1") (pintype "bidirectional"))
      (node (ref "J4") (pin "1") (pinfunction "1_1") (pintype "bidirectional"))
      (node (ref "J5") (pin "1") (pinfunction "1_1") (pintype "bidirectional"))
      (node (ref "U$1") (pin "5V") (pinfunction "5V_5V") (pintype "bidirectional"))
      (node (ref "U$2") (pin "OUT+") (pinfunction "OUT+_OUT+") (pintype "bidirectional"))
    )
    (net (code "41") (name "VCC_12V") (class "Default")
      (node (ref "IC6") (pin "3") (pinfunction "IP-_3") (pintype "passive"))
      (node (ref "IC6") (pin "4") (pinfunction "IP-1_4") (pintype "passive"))
      (node (ref "J1") (pin "2") (pinfunction "2_2") (pintype "passive"))
      (node (ref "R9") (pin "1") (pinfunction "1_1") (pintype "passive"))
      (node (ref "U$2") (pin "IN+") (pinfunction "IN+_IN+") (pintype "bidirectional"))
    )
    (net (code "42") (name "VCC_BBANK") (class "Default")
      (node (ref "BBANK") (pin "1") (pinfunction "1_1") (pintype "bidirectional"))
      (node (ref "R5") (pin "1") (pinfunction "1_1") (pintype "passive"))
    )
    (net (code "43") (name "VCC_PV") (class "Default")
      (node (ref "R7") (pin "1") (pinfunction "1_1") (pintype "passive"))
      (node (ref "VPV") (pin "1") (pinfunction "1_1") (pintype "bidirectional"))
    )
    (net (code "44") (name "unconnected-(IC1-NC-Pad4)") (class "Default")
      (node (ref "IC1") (pin "4") (pinfunction "NC_4") (pintype "no_connect"))
    )
    (net (code "45") (name "unconnected-(IC5-ALERT{slash}RDY-Pad2)") (class "Default")
      (node (ref "IC5") (pin "2") (pinfunction "ALERT/RDY_2") (pintype "bidirectional"))
    )
    (net (code "46") (name "unconnected-(IC8-NC_1-Pad1)") (class "Default")
      (node (ref "IC8") (pin "1") (pinfunction "NC_1_1") (pintype "bidirectional"))
    )
    (net (code "47") (name "unconnected-(IC8-NC_2-Pad5)") (class "Default")
      (node (ref "IC8") (pin "5") (pinfunction "NC_2_5") (pintype "bidirectional"))
    )
    (net (code "48") (name "~{RXEN}") (class "Default")
      (node (ref "IC7") (pin "2") (pinfunction "~{RE}_2") (pintype "bidirectional"))
      (node (ref "R12") (pin "1") (pinfunction "1_1") (pintype "passive"))
      (node (ref "U$1") (pin "23") (pinfunction "23_23") (pintype "bidirectional"))
    )
  )
)
